# DCDC_for_Sensor_9V.net
KiCad netlist of a schematic drawn in EAGLE
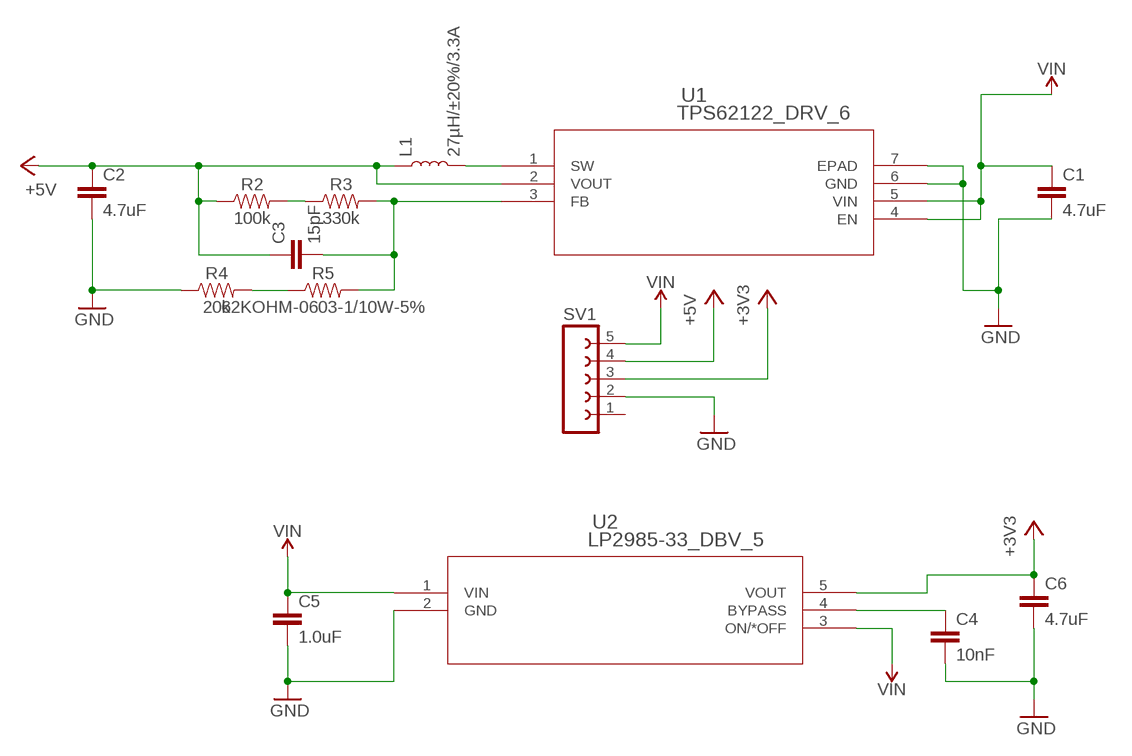
[diagram p0: schematic, sheet 1]

(export (version "E")
  (design (tool "Eeschema 10.0.6"))
  (components
    (comp (ref "C1")
      (value "4.7uF")
      (footprint "eagle-import:1206")
      (libsource (lib "eagle-import") (part "4.7UF-1206-16V-(+80/-20%)"))
    )
    (comp (ref "C2")
      (value "4.7uF")
      (footprint "eagle-import:1206")
      (libsource (lib "eagle-import") (part "4.7UF-1206-16V-(+80/-20%)"))
    )
    (comp (ref "C3")
      (value "15pF")
      (footprint "eagle-import:0603")
      (libsource (lib "eagle-import") (part "15PF-0603-50V-5%"))
    )
    (comp (ref "C4")
      (value "10nF")
      (footprint "eagle-import:0603")
      (libsource (lib "eagle-import") (part "10NF-0603-50V-10%"))
    )
    (comp (ref "C5")
      (value "1.0uF")
      (footprint "eagle-import:0603")
      (libsource (lib "eagle-import") (part "1.0UF-0603-16V-10%"))
    )
    (comp (ref "C6")
      (value "4.7uF")
      (footprint "eagle-import:0603")
      (libsource (lib "eagle-import") (part "4.7UF0603"))
    )
    (comp (ref "L1")
      (value "27µH/±20%/3.3A")
      (footprint "eagle-import:INDUCTOR_SDR1307")
      (libsource (lib "eagle-import") (part "INDUCTOR-SDR13-27UH"))
    )
    (comp (ref "R2")
      (value "100k")
      (footprint "eagle-import:0603")
      (libsource (lib "eagle-import") (part "100KOHM-0603-1/10W-1%"))
    )
    (comp (ref "R3")
      (value "330k")
      (footprint "eagle-import:0603")
      (libsource (lib "eagle-import") (part "330KOHM-0603-1/10W-1%"))
    )
    (comp (ref "R4")
      (value "20k")
      (footprint "eagle-import:0603")
      (libsource (lib "eagle-import") (part "20KOHM-0603-1/10W-5%"))
    )
    (comp (ref "R5")
      (value "62KOHM-0603-1/10W-5%")
      (footprint "eagle-import:0603")
      (libsource (lib "eagle-import") (part "62KOHM-0603-1/10W-5%"))
    )
    (comp (ref "SV1")
      (value "FE05-1")
      (footprint "eagle-import:FE05-1")
      (libsource (lib "eagle-import") (part "FE05-1"))
    )
    (comp (ref "U1")
      (value "TPS62122_DRV_6")
      (footprint "eagle-import:DRV6_1P6X1")
      (fields
        (field (name "GENERIC_PART_NUMBER") "TPS62122")
        (field (name "MANUFACTURER") "Texas Instruments")
        (field (name "MANUFACTURER_PART_NUMBER") "tps62122_drv_6")
      )
      (libsource (lib "eagle-import") (part "TPS62122_DRV_6"))
    )
    (comp (ref "U2")
      (value "LP2985-33_DBV_5")
      (footprint "eagle-import:DBV5")
      (fields
        (field (name "GENERIC_PART_NUMBER") "LP298533")
        (field (name "MANUFACTURER") "Texas Instruments")
        (field (name "MANUFACTURER_PART_NUMBER") "lp298533_dbv_5")
      )
      (libsource (lib "eagle-import") (part "LP2985-33_DBV_5"))
    )
  )
  (nets
    (net (code "1") (name "+3V3") (class "Default")
      (node (ref "C6") (pin "1") (pinfunction "1_1") (pintype "passive"))
      (node (ref "SV1") (pin "3") (pinfunction "3_3") (pintype "passive"))
      (node (ref "U2") (pin "5") (pinfunction "VOUT_5") (pintype "output"))
    )
    (net (code "2") (name "+5V") (class "Default")
      (node (ref "C2") (pin "1") (pinfunction "1_1") (pintype "passive"))
      (node (ref "C3") (pin "1") (pinfunction "1_1") (pintype "passive"))
      (node (ref "L1") (pin "P$1") (pinfunction "1_P$1") (pintype "passive"))
      (node (ref "R2") (pin "1") (pinfunction "1_1") (pintype "passive"))
      (node (ref "SV1") (pin "4") (pinfunction "4_4") (pintype "passive"))
      (node (ref "U1") (pin "2") (pinfunction "VOUT_2") (pintype "input"))
    )
    (net (code "3") (name "GND") (class "Default")
      (node (ref "C1") (pin "2") (pinfunction "2_2") (pintype "passive"))
      (node (ref "C2") (pin "2") (pinfunction "2_2") (pintype "passive"))
      (node (ref "C4") (pin "2") (pinfunction "2_2") (pintype "passive"))
      (node (ref "C5") (pin "2") (pinfunction "2_2") (pintype "passive"))
      (node (ref "C6") (pin "2") (pinfunction "2_2") (pintype "passive"))
      (node (ref "R4") (pin "1") (pinfunction "1_1") (pintype "passive"))
      (node (ref "SV1") (pin "2") (pinfunction "2_2") (pintype "passive"))
      (node (ref "U1") (pin "6") (pinfunction "GND_6") (pintype "power_in"))
      (node (ref "U1") (pin "7") (pinfunction "EPAD_7") (pintype "passive"))
      (node (ref "U2") (pin "2") (pinfunction "GND_2") (pintype "power_in"))
    )
    (net (code "4") (name "Net-(L1-2)") (class "Default")
      (node (ref "L1") (pin "P$2") (pinfunction "2_P$2") (pintype "passive"))
      (node (ref "U1") (pin "1") (pinfunction "SW_1") (pintype "output"))
    )
    (net (code "5") (name "Net-(R2-Pad2)") (class "Default")
      (node (ref "R2") (pin "2") (pinfunction "2_2") (pintype "passive"))
      (node (ref "R3") (pin "1") (pinfunction "1_1") (pintype "passive"))
    )
    (net (code "6") (name "Net-(R4-Pad2)") (class "Default")
      (node (ref "R4") (pin "2") (pinfunction "2_2") (pintype "passive"))
      (node (ref "R5") (pin "1") (pinfunction "1_1") (pintype "passive"))
    )
    (net (code "7") (name "Net-(U1-FB)") (class "Default")
      (node (ref "C3") (pin "2") (pinfunction "2_2") (pintype "passive"))
      (node (ref "R3") (pin "2") (pinfunction "2_2") (pintype "passive"))
      (node (ref "R5") (pin "2") (pinfunction "2_2") (pintype "passive"))
      (node (ref "U1") (pin "3") (pinfunction "FB_3") (pintype "input"))
    )
    (net (code "8") (name "Net-(U2-BYPASS)") (class "Default")
      (node (ref "C4") (pin "1") (pinfunction "1_1") (pintype "passive"))
      (node (ref "U2") (pin "4") (pinfunction "BYPASS_4") (pintype "passive"))
    )
    (net (code "9") (name "VIN") (class "Default")
      (node (ref "C1") (pin "1") (pinfunction "1_1") (pintype "passive"))
      (node (ref "C5") (pin "1") (pinfunction "1_1") (pintype "passive"))
      (node (ref "SV1") (pin "5") (pinfunction "5_5") (pintype "passive"))
      (node (ref "U1") (pin "4") (pinfunction "EN_4") (pintype "input"))
      (node (ref "U1") (pin "5") (pinfunction "VIN_5") (pintype "power_in"))
      (node (ref "U2") (pin "1") (pinfunction "VIN_1") (pintype "input"))
      (node (ref "U2") (pin "3") (pinfunction "ON/*OFF_3") (pintype "passive"))
    )
    (net (code "10") (name "unconnected-(SV1-Pad1)") (class "Default")
      (node (ref "SV1") (pin "1") (pinfunction "1_1") (pintype "passive"))
    )
  )
)
